# 1-Schematic_PCB_Quadcopter_Mugiwara_Pira.net
KiCad netlist of a schematic drawn in EasyEDA
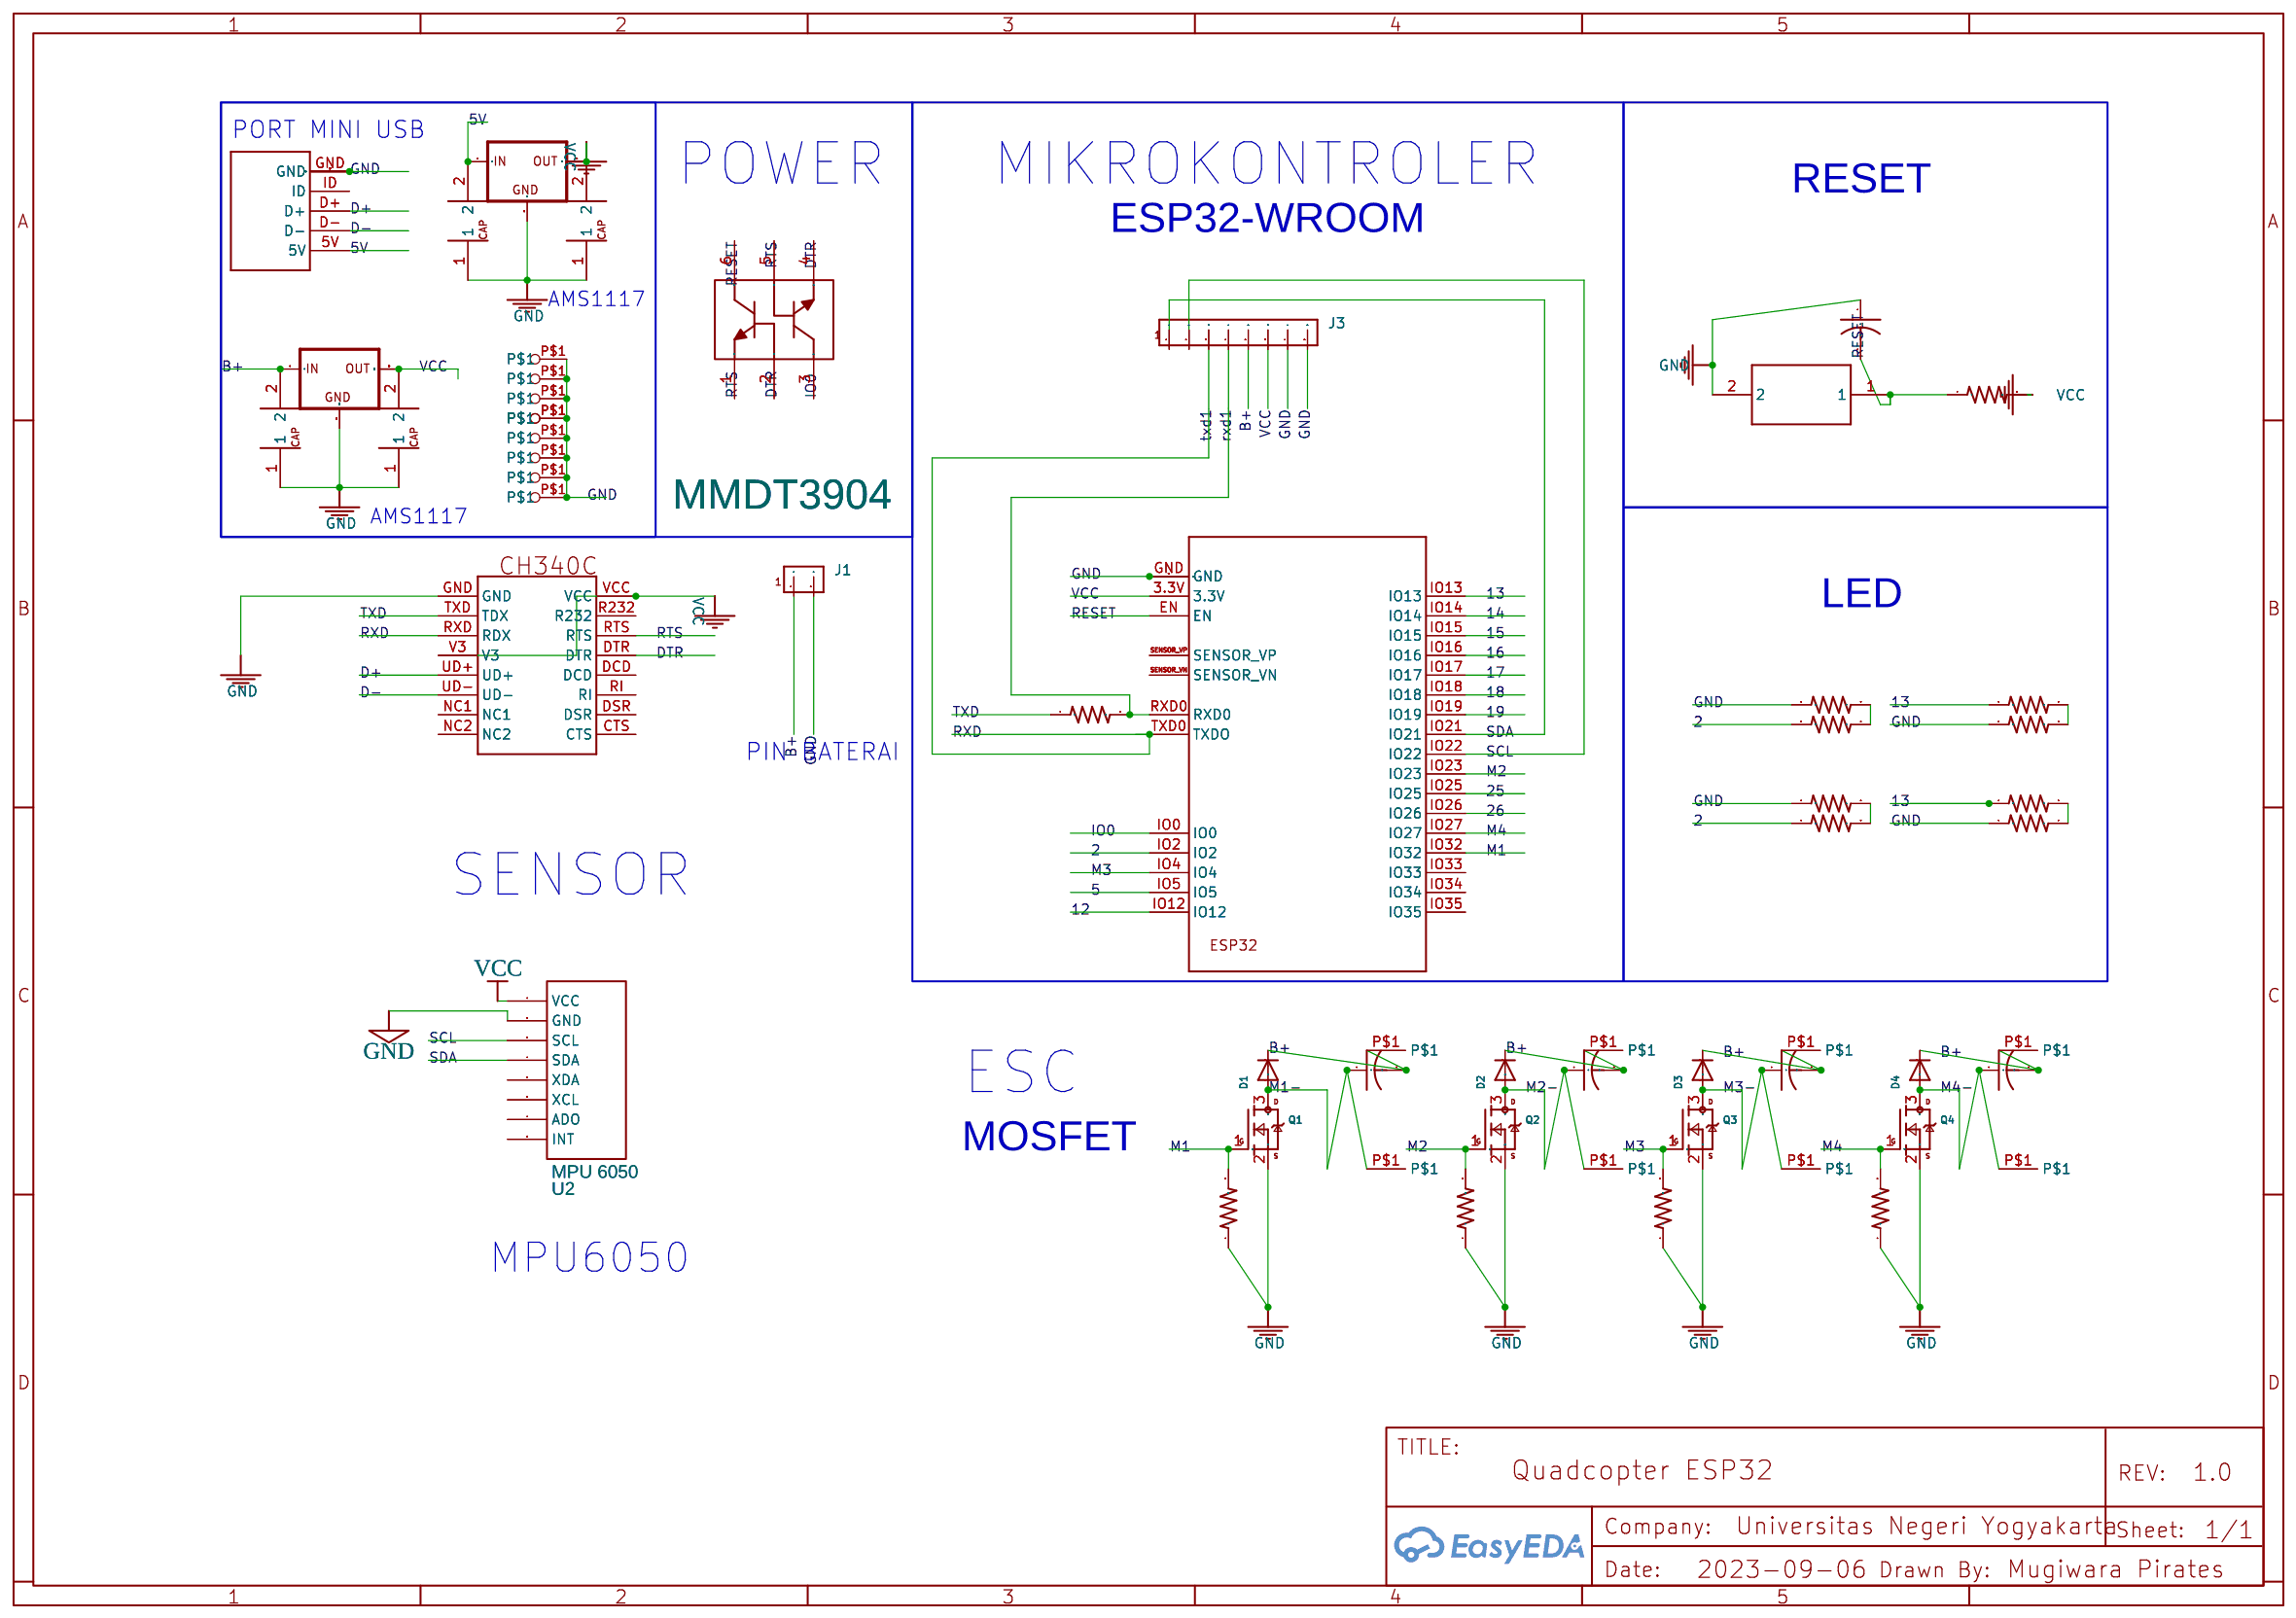
[diagram p0: schematic sheet]

(export (version "E")
  (design (tool "Eeschema 10.0.6"))
  (components
    (comp (ref "D1") (value "DIODESOD-323F") (libsource (lib "") (part "Unknown_635_-275")))
    (comp (ref "D2") (value "DIODESOD-323F") (libsource (lib "") (part "Unknown_755_-275")))
    (comp (ref "D3") (value "DIODESOD-323F") (libsource (lib "") (part "Unknown_855_-275")))
    (comp (ref "D4") (value "DIODESOD-323F") (libsource (lib "") (part "Unknown_965_-275")))
    (comp (ref "IC2") (value "SELF_VREGMP3.3") (libsource (lib "") (part "Unknown_260_-735")))
    (comp (ref "IC3") (value "SELF_VREGMP3.3") (libsource (lib "") (part "Unknown_165_-630")))
    (comp (ref "J1") (value "MTA02-100") (libsource (lib "") (part "Unknown_395_-525")))
    (comp (ref "J3") (value "MTA08-100") (libsource (lib "") (part "Unknown_615_-650")))
    (comp (ref "Q1") (value "MOSFET-NREFLOW") (libsource (lib "") (part "Unknown_625_-245")))
    (comp (ref "Q2") (value "MOSFET-NREFLOW") (libsource (lib "") (part "Unknown_745_-245")))
    (comp (ref "Q3") (value "MOSFET-NREFLOW") (libsource (lib "") (part "Unknown_845_-245")))
    (comp (ref "Q4") (value "MOSFET-NREFLOW") (libsource (lib "") (part "Unknown_955_-245")))
    (comp (ref "U$1") (value "MICROUSB") (libsource (lib "") (part "Unknown_140_-710")))
    (comp (ref "U$2") (value "CH340C") (libsource (lib "") (part "Unknown_265_-475")))
    (comp (ref "U$13") (value "SELF_CAP_0603SELF_CAP_0805") (libsource (lib "") (part "Unknown_230_-725")))
    (comp (ref "U$14") (value "SELF_CAP_0603SELF_CAP_0805") (libsource (lib "") (part "Unknown_290_-725")))
    (comp (ref "U$16") (value "R-US_R0603") (libsource (lib "") (part "Unknown_545_-455")))
    (comp (ref "U$18") (value "SELF_CAP_0603SELF_CAP_0805") (libsource (lib "") (part "Unknown_195_-620")))
    (comp (ref "U$19") (value "SELF_CAP_0603SELF_CAP_0805") (libsource (lib "") (part "Unknown_135_-620")))
    (comp (ref "U$20") (value "R-US_R0603") (libsource (lib "") (part "Unknown_615_-205")))
    (comp (ref "U$21") (value "R-US_R0603") (libsource (lib "") (part "Unknown_735_-205")))
    (comp (ref "U$22") (value "R-US_R0603") (libsource (lib "") (part "Unknown_835_-205")))
    (comp (ref "U$23") (value "R-US_R0603") (libsource (lib "") (part "Unknown_945_-205")))
    (comp (ref "U$24") (value "C-USC0603") (libsource (lib "") (part "Unknown_685_-275")))
    (comp (ref "U$25") (value "C-USC0603") (libsource (lib "") (part "Unknown_1005_-275")))
    (comp (ref "U$26") (value "C-USC0603") (libsource (lib "") (part "Unknown_795_-275")))
    (comp (ref "U$27") (value "C-USC0603") (libsource (lib "") (part "Unknown_895_-275")))
    (comp (ref "U$29") (value "SELF_PUSHBUTTON") (libsource (lib "") (part "Unknown_900_-612")))
    (comp (ref "U$30") (value "R-US_R0603") (libsource (lib "") (part "Unknown_999_-617")))
    (comp (ref "U$31") (value "C-USC0603") (libsource (lib "") (part "Unknown_935_-655")))
    (comp (ref "U$32") (value "R-US_R0603") (libsource (lib "") (part "Unknown_920_-460")))
    (comp (ref "U$33") (value "R-US_R0603") (libsource (lib "") (part "Unknown_920_-450")))
    (comp (ref "U$34") (value "R-US_R0603") (libsource (lib "") (part "Unknown_1020_-460")))
    (comp (ref "U$35") (value "R-US_R0603") (libsource (lib "") (part "Unknown_1020_-450")))
    (comp (ref "U$36") (value "R-US_R0603") (libsource (lib "") (part "Unknown_1020_-410")))
    (comp (ref "U$37") (value "R-US_R0603") (libsource (lib "") (part "Unknown_1020_-400")))
    (comp (ref "U$38") (value "R-US_R0603") (libsource (lib "") (part "Unknown_920_-410")))
    (comp (ref "U$39") (value "R-US_R0603") (libsource (lib "") (part "Unknown_920_-400")))
    (comp (ref "U$40") (value "SELF_PINOUTS") (libsource (lib "") (part "Unknown_685_-285")))
    (comp (ref "U$41") (value "SELF_PINOUTS") (libsource (lib "") (part "Unknown_685_-225")))
    (comp (ref "U$42") (value "SELF_PINOUTS") (libsource (lib "") (part "Unknown_795_-285")))
    (comp (ref "U$43") (value "SELF_PINOUTS") (libsource (lib "") (part "Unknown_795_-225")))
    (comp (ref "U$44") (value "SELF_PINOUTS") (libsource (lib "") (part "Unknown_895_-285")))
    (comp (ref "U$45") (value "SELF_PINOUTS") (libsource (lib "") (part "Unknown_895_-225")))
    (comp (ref "U$46") (value "SELF_PINOUTS") (libsource (lib "") (part "Unknown_1005_-285")))
    (comp (ref "U$47") (value "SELF_PINOUTS") (libsource (lib "") (part "Unknown_1005_-225")))
    (comp (ref "U$48") (value "SELF_PIN2") (libsource (lib "") (part "Unknown_270_-635")))
    (comp (ref "U$49") (value "SELF_PIN2") (libsource (lib "") (part "Unknown_270_-625")))
    (comp (ref "U$50") (value "SELF_PIN2") (libsource (lib "") (part "Unknown_270_-615")))
    (comp (ref "U$51") (value "SELF_PIN2") (libsource (lib "") (part "Unknown_270_-605")))
    (comp (ref "U$52") (value "SELF_PIN2") (libsource (lib "") (part "Unknown_270_-605")))
    (comp (ref "U$53") (value "SELF_PIN2") (libsource (lib "") (part "Unknown_270_-595")))
    (comp (ref "U$54") (value "SELF_PIN2") (libsource (lib "") (part "Unknown_270_-575")))
    (comp (ref "U$55") (value "SELF_PIN2") (libsource (lib "") (part "Unknown_270_-565")))
    (comp (ref "U$56") (value "SELF_PIN2") (libsource (lib "") (part "Unknown_270_-585")))
    (comp (ref "U1") (value "ESP32") (libsource (lib "") (part "Unknown_655_-435")))
    (comp (ref "U2") (value "MPU 6050") (libsource (lib "") (part "MPU 6050")))
    (comp (ref "U3")
      (value "MMDT3904")
      (fields (field (name "Manufacturer Part") "MMDT3904Q-7-F") (field (name "Manufacturer") "DIODES(美台)"))
      (libsource (lib "") (part "MMDT3904Q-7-F"))
    )
  )
  (nets
    (net (code "1") (name "/2") (class "Default")
      (node (ref "U$33") (pin "1") (pinfunction "1_1") (pintype "bidirectional"))
      (node (ref "U$39") (pin "1") (pinfunction "1_1") (pintype "bidirectional"))
      (node (ref "U1") (pin "IO2") (pinfunction "IO2_IO2") (pintype "bidirectional"))
    )
    (net (code "2") (name "/5") (class "Default")
      (node (ref "U1") (pin "IO5") (pinfunction "IO5_IO5") (pintype "bidirectional"))
    )
    (net (code "3") (name "/5V") (class "Default")
      (node (ref "IC2") (pin "VIN") (pinfunction "IN_VIN") (pintype "bidirectional"))
      (node (ref "U$1") (pin "5V") (pinfunction "5V_5V") (pintype "bidirectional"))
      (node (ref "U$13") (pin "2") (pinfunction "2_2") (pintype "bidirectional"))
    )
    (net (code "4") (name "/12") (class "Default")
      (node (ref "U1") (pin "IO12") (pinfunction "IO12_IO12") (pintype "bidirectional"))
    )
    (net (code "5") (name "/13") (class "Default")
      (node (ref "U$34") (pin "1") (pinfunction "1_1") (pintype "bidirectional"))
      (node (ref "U$36") (pin "1") (pinfunction "1_1") (pintype "bidirectional"))
      (node (ref "U1") (pin "IO13") (pinfunction "IO13_IO13") (pintype "bidirectional"))
    )
    (net (code "6") (name "/14") (class "Default")
      (node (ref "U1") (pin "IO14") (pinfunction "IO14_IO14") (pintype "bidirectional"))
    )
    (net (code "7") (name "/15") (class "Default")
      (node (ref "U1") (pin "IO15") (pinfunction "IO15_IO15") (pintype "bidirectional"))
    )
    (net (code "8") (name "/16") (class "Default")
      (node (ref "U1") (pin "IO16") (pinfunction "IO16_IO16") (pintype "bidirectional"))
    )
    (net (code "9") (name "/17") (class "Default")
      (node (ref "U1") (pin "IO17") (pinfunction "IO17_IO17") (pintype "bidirectional"))
    )
    (net (code "10") (name "/18") (class "Default")
      (node (ref "U1") (pin "IO18") (pinfunction "IO18_IO18") (pintype "bidirectional"))
    )
    (net (code "11") (name "/19") (class "Default")
      (node (ref "U1") (pin "IO19") (pinfunction "IO19_IO19") (pintype "bidirectional"))
    )
    (net (code "12") (name "/25") (class "Default")
      (node (ref "U1") (pin "IO25") (pinfunction "IO25_IO25") (pintype "bidirectional"))
    )
    (net (code "13") (name "/26") (class "Default")
      (node (ref "U1") (pin "IO26") (pinfunction "IO26_IO26") (pintype "bidirectional"))
    )
    (net (code "14") (name "/B+") (class "Default")
      (node (ref "D1") (pin "C") (pinfunction "C_C") (pintype "bidirectional"))
      (node (ref "D2") (pin "C") (pinfunction "C_C") (pintype "bidirectional"))
      (node (ref "IC3") (pin "VIN") (pinfunction "IN_VIN") (pintype "bidirectional"))
      (node (ref "J1") (pin "1") (pinfunction "1_1") (pintype "bidirectional"))
      (node (ref "J3") (pin "5") (pinfunction "5_5") (pintype "bidirectional"))
      (node (ref "U$19") (pin "2") (pinfunction "2_2") (pintype "bidirectional"))
      (node (ref "U$24") (pin "2") (pinfunction "2_2") (pintype "bidirectional"))
      (node (ref "U$26") (pin "2") (pinfunction "2_2") (pintype "bidirectional"))
      (node (ref "U$40") (pin "P$1") (pinfunction "P$1_P$1") (pintype "bidirectional"))
      (node (ref "U$42") (pin "P$1") (pinfunction "P$1_P$1") (pintype "bidirectional"))
    )
    (net (code "15") (name "/D+") (class "Default")
      (node (ref "U$1") (pin "D+") (pinfunction "D+_D+") (pintype "bidirectional"))
      (node (ref "U$2") (pin "UD+") (pinfunction "UD+_UD+") (pintype "bidirectional"))
    )
    (net (code "16") (name "/D-") (class "Default")
      (node (ref "U$1") (pin "D-") (pinfunction "D-_D-") (pintype "bidirectional"))
      (node (ref "U$2") (pin "UD-") (pinfunction "UD-_UD-") (pintype "bidirectional"))
    )
    (net (code "17") (name "/DTR") (class "Default")
      (node (ref "U$2") (pin "DTR") (pinfunction "DTR_DTR") (pintype "bidirectional"))
      (node (ref "U3") (pin "2") (pinfunction "B2_2") (pintype "unspecified"))
      (node (ref "U3") (pin "4") (pinfunction "E1_4") (pintype "unspecified"))
    )
    (net (code "18") (name "/IO0") (class "Default")
      (node (ref "U1") (pin "IO0") (pinfunction "IO0_IO0") (pintype "bidirectional"))
      (node (ref "U3") (pin "3") (pinfunction "C1_3") (pintype "unspecified"))
    )
    (net (code "19") (name "/M1") (class "Default")
      (node (ref "Q1") (pin "1") (pinfunction "G_1") (pintype "bidirectional"))
      (node (ref "U$20") (pin "2") (pinfunction "2_2") (pintype "bidirectional"))
      (node (ref "U1") (pin "IO32") (pinfunction "IO32_IO32") (pintype "bidirectional"))
    )
    (net (code "20") (name "/M1-") (class "Default")
      (node (ref "D1") (pin "A") (pinfunction "A_A") (pintype "bidirectional"))
      (node (ref "Q1") (pin "3") (pinfunction "D_3") (pintype "bidirectional"))
      (node (ref "U$24") (pin "1") (pinfunction "1_1") (pintype "bidirectional"))
      (node (ref "U$41") (pin "P$1") (pinfunction "P$1_P$1") (pintype "bidirectional"))
    )
    (net (code "21") (name "/M2") (class "Default")
      (node (ref "Q2") (pin "1") (pinfunction "G_1") (pintype "bidirectional"))
      (node (ref "U$21") (pin "2") (pinfunction "2_2") (pintype "bidirectional"))
      (node (ref "U1") (pin "IO23") (pinfunction "IO23_IO23") (pintype "bidirectional"))
    )
    (net (code "22") (name "/M2-") (class "Default")
      (node (ref "D2") (pin "A") (pinfunction "A_A") (pintype "bidirectional"))
      (node (ref "Q2") (pin "3") (pinfunction "D_3") (pintype "bidirectional"))
      (node (ref "U$26") (pin "1") (pinfunction "1_1") (pintype "bidirectional"))
      (node (ref "U$43") (pin "P$1") (pinfunction "P$1_P$1") (pintype "bidirectional"))
    )
    (net (code "23") (name "/M3") (class "Default")
      (node (ref "Q3") (pin "1") (pinfunction "G_1") (pintype "bidirectional"))
      (node (ref "U$22") (pin "2") (pinfunction "2_2") (pintype "bidirectional"))
      (node (ref "U1") (pin "IO4") (pinfunction "IO4_IO4") (pintype "bidirectional"))
    )
    (net (code "24") (name "/M3-") (class "Default")
      (node (ref "D3") (pin "A") (pinfunction "A_A") (pintype "bidirectional"))
      (node (ref "Q3") (pin "3") (pinfunction "D_3") (pintype "bidirectional"))
      (node (ref "U$27") (pin "1") (pinfunction "1_1") (pintype "bidirectional"))
      (node (ref "U$45") (pin "P$1") (pinfunction "P$1_P$1") (pintype "bidirectional"))
    )
    (net (code "25") (name "/M4") (class "Default")
      (node (ref "Q4") (pin "1") (pinfunction "G_1") (pintype "bidirectional"))
      (node (ref "U$23") (pin "2") (pinfunction "2_2") (pintype "bidirectional"))
      (node (ref "U1") (pin "IO27") (pinfunction "IO27_IO27") (pintype "bidirectional"))
    )
    (net (code "26") (name "/M4-") (class "Default")
      (node (ref "D4") (pin "A") (pinfunction "A_A") (pintype "bidirectional"))
      (node (ref "Q4") (pin "3") (pinfunction "D_3") (pintype "bidirectional"))
      (node (ref "U$25") (pin "1") (pinfunction "1_1") (pintype "bidirectional"))
      (node (ref "U$47") (pin "P$1") (pinfunction "P$1_P$1") (pintype "bidirectional"))
    )
    (net (code "27") (name "/RESET") (class "Default")
      (node (ref "U$29") (pin "1") (pinfunction "1_1") (pintype "bidirectional"))
      (node (ref "U$30") (pin "1") (pinfunction "1_1") (pintype "bidirectional"))
      (node (ref "U$31") (pin "2") (pinfunction "2_2") (pintype "bidirectional"))
      (node (ref "U1") (pin "EN") (pinfunction "EN_EN") (pintype "bidirectional"))
      (node (ref "U3") (pin "6") (pinfunction "C2_6") (pintype "unspecified"))
    )
    (net (code "28") (name "/RTS") (class "Default")
      (node (ref "U$2") (pin "RTS") (pinfunction "RTS_RTS") (pintype "bidirectional"))
      (node (ref "U3") (pin "1") (pinfunction "E2_1") (pintype "unspecified"))
      (node (ref "U3") (pin "5") (pinfunction "B1_5") (pintype "unspecified"))
    )
    (net (code "29") (name "/RXD") (class "Default")
      (node (ref "J3") (pin "3") (pinfunction "3_3") (pintype "bidirectional"))
      (node (ref "U$2") (pin "RXD") (pinfunction "RDX_RXD") (pintype "bidirectional"))
      (node (ref "U1") (pin "TXD0") (pinfunction "TXDO_TXD0") (pintype "bidirectional"))
    )
    (net (code "30") (name "/SCL") (class "Default")
      (node (ref "J3") (pin "2") (pinfunction "2_2") (pintype "bidirectional"))
      (node (ref "U1") (pin "IO22") (pinfunction "IO22_IO22") (pintype "bidirectional"))
      (node (ref "U2") (pin "3") (pinfunction "SCL_3") (pintype "unspecified"))
    )
    (net (code "31") (name "/SDA") (class "Default")
      (node (ref "J3") (pin "1") (pinfunction "1_1") (pintype "bidirectional"))
      (node (ref "U1") (pin "IO21") (pinfunction "IO21_IO21") (pintype "bidirectional"))
      (node (ref "U2") (pin "4") (pinfunction "SDA_4") (pintype "unspecified"))
    )
    (net (code "32") (name "/TXD") (class "Default")
      (node (ref "U$16") (pin "1") (pinfunction "1_1") (pintype "bidirectional"))
      (node (ref "U$2") (pin "TXD") (pinfunction "TDX_TXD") (pintype "bidirectional"))
    )
    (net (code "33") (name "/rxd1") (class "Default")
      (node (ref "J3") (pin "4") (pinfunction "4_4") (pintype "bidirectional"))
      (node (ref "U$16") (pin "2") (pinfunction "2_2") (pintype "bidirectional"))
      (node (ref "U1") (pin "RXD0") (pinfunction "RXD0_RXD0") (pintype "bidirectional"))
    )
    (net (code "34") (name "GND") (class "Default")
      (node (ref "IC2") (pin "GND") (pinfunction "GND_GND") (pintype "bidirectional"))
      (node (ref "IC3") (pin "GND") (pinfunction "GND_GND") (pintype "bidirectional"))
      (node (ref "J1") (pin "2") (pinfunction "2_2") (pintype "bidirectional"))
      (node (ref "J3") (pin "7") (pinfunction "7_7") (pintype "bidirectional"))
      (node (ref "J3") (pin "8") (pinfunction "8_8") (pintype "bidirectional"))
      (node (ref "Q1") (pin "2") (pinfunction "S_2") (pintype "bidirectional"))
      (node (ref "Q2") (pin "2") (pinfunction "S_2") (pintype "bidirectional"))
      (node (ref "Q3") (pin "2") (pinfunction "S_2") (pintype "bidirectional"))
      (node (ref "Q4") (pin "2") (pinfunction "S_2") (pintype "bidirectional"))
      (node (ref "U$1") (pin "GND") (pinfunction "GND_GND") (pintype "bidirectional"))
      (node (ref "U$1") (pin "GND1") (pinfunction "GND_GND1") (pintype "bidirectional"))
      (node (ref "U$1") (pin "GND2") (pinfunction "GND_GND2") (pintype "bidirectional"))
      (node (ref "U$1") (pin "GND3") (pinfunction "GND_GND3") (pintype "bidirectional"))
      (node (ref "U$1") (pin "GND4") (pinfunction "GND_GND4") (pintype "bidirectional"))
      (node (ref "U$1") (pin "GND5") (pinfunction "GND_GND5") (pintype "bidirectional"))
      (node (ref "U$1") (pin "GND6") (pinfunction "GND_GND6") (pintype "bidirectional"))
      (node (ref "U$13") (pin "1") (pinfunction "1_1") (pintype "bidirectional"))
      (node (ref "U$14") (pin "1") (pinfunction "1_1") (pintype "bidirectional"))
      (node (ref "U$18") (pin "1") (pinfunction "1_1") (pintype "bidirectional"))
      (node (ref "U$19") (pin "1") (pinfunction "1_1") (pintype "bidirectional"))
      (node (ref "U$2") (pin "GND") (pinfunction "GND_GND") (pintype "bidirectional"))
      (node (ref "U$20") (pin "1") (pinfunction "1_1") (pintype "bidirectional"))
      (node (ref "U$21") (pin "1") (pinfunction "1_1") (pintype "bidirectional"))
      (node (ref "U$22") (pin "1") (pinfunction "1_1") (pintype "bidirectional"))
      (node (ref "U$23") (pin "1") (pinfunction "1_1") (pintype "bidirectional"))
      (node (ref "U$29") (pin "2") (pinfunction "2_2") (pintype "bidirectional"))
      (node (ref "U$31") (pin "1") (pinfunction "1_1") (pintype "bidirectional"))
      (node (ref "U$32") (pin "1") (pinfunction "1_1") (pintype "bidirectional"))
      (node (ref "U$35") (pin "1") (pinfunction "1_1") (pintype "bidirectional"))
      (node (ref "U$37") (pin "1") (pinfunction "1_1") (pintype "bidirectional"))
      (node (ref "U$38") (pin "1") (pinfunction "1_1") (pintype "bidirectional"))
      (node (ref "U$48") (pin "P$1") (pinfunction "P$1_P$1") (pintype "bidirectional"))
      (node (ref "U$49") (pin "P$1") (pinfunction "P$1_P$1") (pintype "bidirectional"))
      (node (ref "U$50") (pin "P$1") (pinfunction "P$1_P$1") (pintype "bidirectional"))
      (node (ref "U$51") (pin "P$1") (pinfunction "P$1_P$1") (pintype "bidirectional"))
      (node (ref "U$52") (pin "P$1") (pinfunction "P$1_P$1") (pintype "bidirectional"))
      (node (ref "U$53") (pin "P$1") (pinfunction "P$1_P$1") (pintype "bidirectional"))
      (node (ref "U$54") (pin "P$1") (pinfunction "P$1_P$1") (pintype "bidirectional"))
      (node (ref "U$55") (pin "P$1") (pinfunction "P$1_P$1") (pintype "bidirectional"))
      (node (ref "U$56") (pin "P$1") (pinfunction "P$1_P$1") (pintype "bidirectional"))
      (node (ref "U1") (pin "GND") (pinfunction "GND_GND") (pintype "bidirectional"))
      (node (ref "U1") (pin "GND1") (pinfunction "GND_GND1") (pintype "bidirectional"))
      (node (ref "U1") (pin "GND2") (pinfunction "GND_GND2") (pintype "bidirectional"))
      (node (ref "U1") (pin "GND3") (pinfunction "GND_GND3") (pintype "bidirectional"))
      (node (ref "U2") (pin "2") (pinfunction "GND_2") (pintype "unspecified"))
    )
    (net (code "35") (name "Net-(D3-PadC)") (class "Default")
      (node (ref "D3") (pin "C") (pinfunction "C_C") (pintype "bidirectional"))
      (node (ref "U$27") (pin "2") (pinfunction "2_2") (pintype "bidirectional"))
      (node (ref "U$44") (pin "P$1") (pinfunction "P$1_P$1") (pintype "bidirectional"))
    )
    (net (code "36") (name "Net-(D4-PadC)") (class "Default")
      (node (ref "D4") (pin "C") (pinfunction "C_C") (pintype "bidirectional"))
      (node (ref "U$25") (pin "2") (pinfunction "2_2") (pintype "bidirectional"))
      (node (ref "U$46") (pin "P$1") (pinfunction "P$1_P$1") (pintype "bidirectional"))
    )
    (net (code "37") (name "Net-(U$32-Pad2)") (class "Default")
      (node (ref "U$32") (pin "2") (pinfunction "2_2") (pintype "bidirectional"))
      (node (ref "U$33") (pin "2") (pinfunction "2_2") (pintype "bidirectional"))
    )
    (net (code "38") (name "Net-(U$34-Pad2)") (class "Default")
      (node (ref "U$34") (pin "2") (pinfunction "2_2") (pintype "bidirectional"))
      (node (ref "U$35") (pin "2") (pinfunction "2_2") (pintype "bidirectional"))
    )
    (net (code "39") (name "Net-(U$36-Pad2)") (class "Default")
      (node (ref "U$36") (pin "2") (pinfunction "2_2") (pintype "bidirectional"))
      (node (ref "U$37") (pin "2") (pinfunction "2_2") (pintype "bidirectional"))
    )
    (net (code "40") (name "Net-(U$38-Pad2)") (class "Default")
      (node (ref "U$38") (pin "2") (pinfunction "2_2") (pintype "bidirectional"))
      (node (ref "U$39") (pin "2") (pinfunction "2_2") (pintype "bidirectional"))
    )
    (net (code "41") (name "VCC") (class "Default")
      (node (ref "IC2") (pin "VOUT") (pinfunction "OUT_VOUT") (pintype "bidirectional"))
      (node (ref "IC2") (pin "VOUT1") (pinfunction "OUT_VOUT1") (pintype "bidirectional"))
      (node (ref "IC3") (pin "VOUT") (pinfunction "OUT_VOUT") (pintype "bidirectional"))
      (node (ref "IC3") (pin "VOUT1") (pinfunction "OUT_VOUT1") (pintype "bidirectional"))
      (node (ref "J3") (pin "6") (pinfunction "6_6") (pintype "bidirectional"))
      (node (ref "U$14") (pin "2") (pinfunction "2_2") (pintype "bidirectional"))
      (node (ref "U$18") (pin "2") (pinfunction "2_2") (pintype "bidirectional"))
      (node (ref "U$2") (pin "V3") (pinfunction "V3_V3") (pintype "bidirectional"))
      (node (ref "U$2") (pin "VCC") (pinfunction "VCC_VCC") (pintype "bidirectional"))
      (node (ref "U$30") (pin "2") (pinfunction "2_2") (pintype "bidirectional"))
      (node (ref "U1") (pin "3.3V") (pinfunction "3.3V_3.3V") (pintype "bidirectional"))
      (node (ref "U2") (pin "1") (pinfunction "VCC_1") (pintype "unspecified"))
    )
    (net (code "42") (name "unconnected-(U$1-PadID)") (class "Default")
      (node (ref "U$1") (pin "ID") (pinfunction "ID_ID") (pintype "bidirectional"))
    )
    (net (code "43") (name "unconnected-(U$2-PadCTS)") (class "Default")
      (node (ref "U$2") (pin "CTS") (pinfunction "CTS_CTS") (pintype "bidirectional"))
    )
    (net (code "44") (name "unconnected-(U$2-PadDCD)") (class "Default")
      (node (ref "U$2") (pin "DCD") (pinfunction "DCD_DCD") (pintype "bidirectional"))
    )
    (net (code "45") (name "unconnected-(U$2-PadDSR)") (class "Default")
      (node (ref "U$2") (pin "DSR") (pinfunction "DSR_DSR") (pintype "bidirectional"))
    )
    (net (code "46") (name "unconnected-(U$2-PadNC1)") (class "Default")
      (node (ref "U$2") (pin "NC1") (pinfunction "NC1_NC1") (pintype "bidirectional"))
    )
    (net (code "47") (name "unconnected-(U$2-PadNC2)") (class "Default")
      (node (ref "U$2") (pin "NC2") (pinfunction "NC2_NC2") (pintype "bidirectional"))
    )
    (net (code "48") (name "unconnected-(U$2-PadR232)") (class "Default")
      (node (ref "U$2") (pin "R232") (pinfunction "R232_R232") (pintype "bidirectional"))
    )
    (net (code "49") (name "unconnected-(U$2-PadRI)") (class "Default")
      (node (ref "U$2") (pin "RI") (pinfunction "RI_RI") (pintype "bidirectional"))
    )
    (net (code "50") (name "unconnected-(U1-PadIO33)") (class "Default")
      (node (ref "U1") (pin "IO33") (pinfunction "IO33_IO33") (pintype "bidirectional"))
    )
    (net (code "51") (name "unconnected-(U1-PadIO34)") (class "Default")
      (node (ref "U1") (pin "IO34") (pinfunction "IO34_IO34") (pintype "bidirectional"))
    )
    (net (code "52") (name "unconnected-(U1-PadIO35)") (class "Default")
      (node (ref "U1") (pin "IO35") (pinfunction "IO35_IO35") (pintype "bidirectional"))
    )
    (net (code "53") (name "unconnected-(U1-PadSENSOR_VN)") (class "Default")
      (node (ref "U1") (pin "SENSOR_VN") (pinfunction "SENSOR_VN_SENSOR_VN") (pintype "bidirectional"))
    )
    (net (code "54") (name "unconnected-(U1-PadSENSOR_VP)") (class "Default")
      (node (ref "U1") (pin "SENSOR_VP") (pinfunction "SENSOR_VP_SENSOR_VP") (pintype "bidirectional"))
    )
    (net (code "55") (name "unconnected-(U2-ADO-Pad7)") (class "Default")
      (node (ref "U2") (pin "7") (pinfunction "ADO_7") (pintype "unspecified"))
    )
    (net (code "56") (name "unconnected-(U2-INT-Pad8)") (class "Default")
      (node (ref "U2") (pin "8") (pinfunction "INT_8") (pintype "unspecified"))
    )
    (net (code "57") (name "unconnected-(U2-XCL-Pad6)") (class "Default")
      (node (ref "U2") (pin "6") (pinfunction "XCL_6") (pintype "unspecified"))
    )
    (net (code "58") (name "unconnected-(U2-XDA-Pad5)") (class "Default")
      (node (ref "U2") (pin "5") (pinfunction "XDA_5") (pintype "unspecified"))
    )
  )
)
